# ISPnub_v1_1.net
KiCad netlist of a schematic drawn in EAGLE
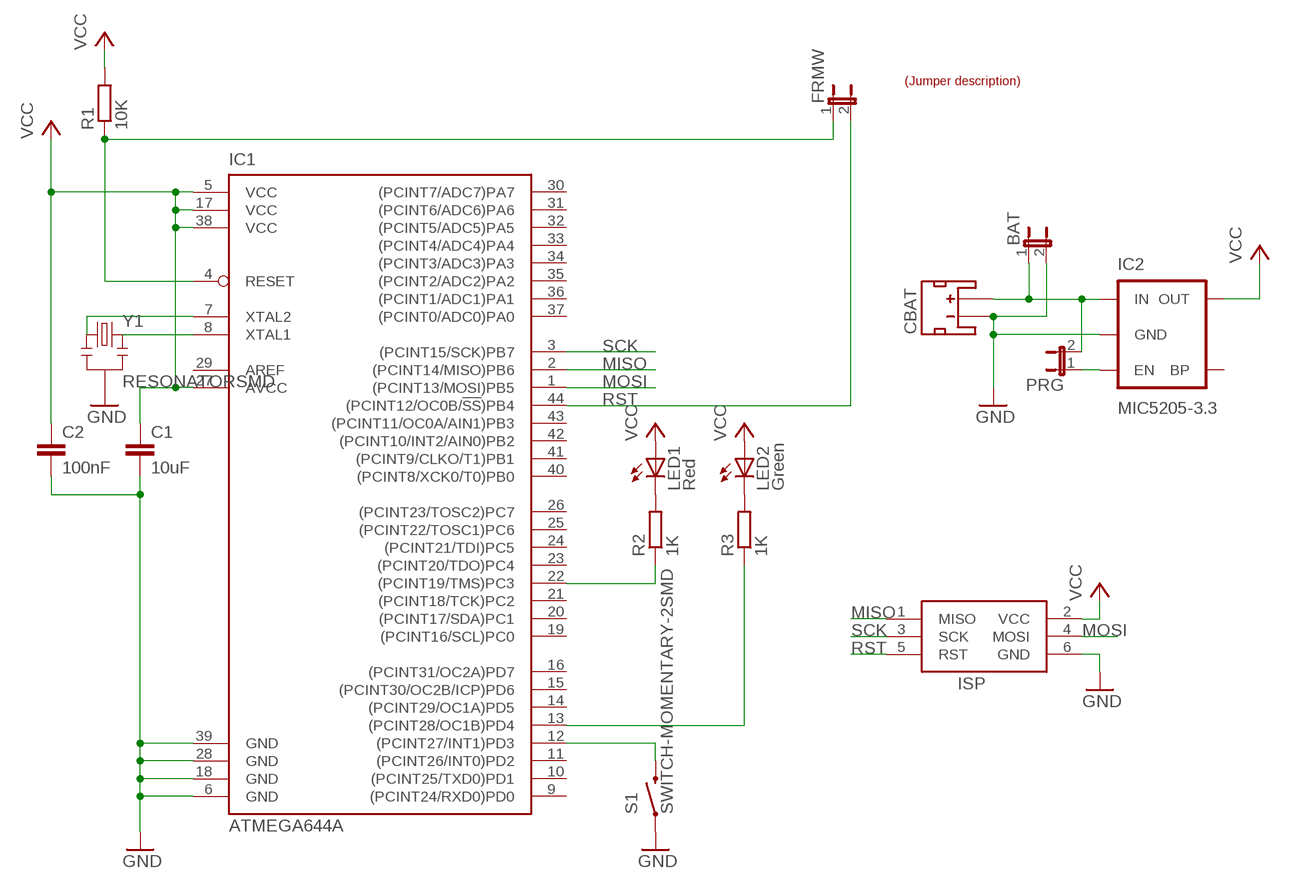
[diagram p0: schematic, sheet 1]

(export (version "E")
  (design (tool "Eeschema 10.0.6"))
  (components
    (comp (ref "BAT")
      (value "JP1E")
      (footprint "eagle-import:JP1")
      (libsource (lib "eagle-import") (part "JP1E"))
    )
    (comp (ref "C1")
      (value "10uF")
      (footprint "eagle-import:C0805")
      (libsource (lib "eagle-import") (part "C-EUC0805"))
    )
    (comp (ref "C2")
      (value "100nF")
      (footprint "eagle-import:C0805")
      (libsource (lib "eagle-import") (part "C-EUC0805"))
    )
    (comp (ref "CBAT")
      (value "JST PH SMT")
      (footprint "eagle-import:JST-2-SMD")
      (libsource (lib "eagle-import") (part "JST_2MM_MALE"))
    )
    (comp (ref "FRMW")
      (value "JP1E")
      (footprint "eagle-import:JP1")
      (libsource (lib "eagle-import") (part "JP1E"))
    )
    (comp (ref "IC1")
      (value "ATMEGA644A")
      (footprint "eagle-import:TQFP44")
      (fields (field (name "MPN") "ATMEGA644PV-10AU") (field (name "MPN_1") "ATMEGA1284PV-10AU"))
      (libsource (lib "eagle-import") (part "ATMEGA644A"))
    )
    (comp (ref "IC2")
      (value "MIC5205-3.3")
      (footprint "eagle-import:SOT23-5")
      (libsource (lib "eagle-import") (part "V_REG_LDOSMD"))
    )
    (comp (ref "ISP")
      (value "AVRISP-6")
      (footprint "eagle-import:AVRISP")
      (libsource (lib "eagle-import") (part "AVRISP-6"))
    )
    (comp (ref "LED1")
      (value "Red")
      (footprint "eagle-import:CHIP-LED0805")
      (libsource (lib "eagle-import") (part "LEDCHIP-LED0805"))
    )
    (comp (ref "LED2")
      (value "Green")
      (footprint "eagle-import:CHIP-LED0805")
      (libsource (lib "eagle-import") (part "LEDCHIP-LED0805"))
    )
    (comp (ref "PRG")
      (value "JP1E")
      (footprint "eagle-import:JP1")
      (libsource (lib "eagle-import") (part "JP1E"))
    )
    (comp (ref "R1")
      (value "10K")
      (footprint "eagle-import:R0805")
      (libsource (lib "eagle-import") (part "R-EU_R0805"))
    )
    (comp (ref "R2")
      (value "1K")
      (footprint "eagle-import:R0805")
      (libsource (lib "eagle-import") (part "R-EU_R0805"))
    )
    (comp (ref "R3")
      (value "1K")
      (footprint "eagle-import:R0805")
      (libsource (lib "eagle-import") (part "R-EU_R0805"))
    )
    (comp (ref "S1")
      (value "SWITCH-MOMENTARY-2SMD")
      (footprint "eagle-import:TACTILE_SWITCH_SMD")
      (libsource (lib "eagle-import") (part "SWITCH-MOMENTARY-2SMD"))
    )
    (comp (ref "U$1")
      (value "LABEL_JUMPER_1X2")
      (footprint "eagle-import:JUMP2_DESC")
      (fields (field (name "OFF") "Normal") (field (name "ON") "Update Firmware"))
      (libsource (lib "eagle-import") (part "LABEL_JUMPER_1X2"))
    )
    (comp (ref "Y1")
      (value "RESONATORSMD")
      (footprint "eagle-import:RESONATOR-SMD")
      (libsource (lib "eagle-import") (part "RESONATORSMD"))
    )
  )
  (nets
    (net (code "1") (name "/MISO") (class "Default")
      (node (ref "IC1") (pin "2") (pinfunction "(PCINT14/MISO)PB6_2") (pintype "bidirectional"))
      (node (ref "ISP") (pin "1") (pinfunction "MISO_1") (pintype "input"))
    )
    (net (code "2") (name "/MOSI") (class "Default")
      (node (ref "IC1") (pin "1") (pinfunction "(PCINT13/MOSI)PB5_1") (pintype "bidirectional"))
      (node (ref "ISP") (pin "4") (pinfunction "MOSI_4") (pintype "output"))
    )
    (net (code "3") (name "/RST") (class "Default")
      (node (ref "FRMW") (pin "2") (pinfunction "2_2") (pintype "passive"))
      (node (ref "IC1") (pin "44") (pinfunction "(PCINT12/OC0B/~{SS})PB4_44") (pintype "bidirectional"))
      (node (ref "ISP") (pin "5") (pinfunction "RST_5") (pintype "output"))
    )
    (net (code "4") (name "/SCK") (class "Default")
      (node (ref "IC1") (pin "3") (pinfunction "(PCINT15/SCK)PB7_3") (pintype "bidirectional"))
      (node (ref "ISP") (pin "3") (pinfunction "SCK_3") (pintype "output"))
    )
    (net (code "5") (name "GND") (class "Default")
      (node (ref "BAT") (pin "2") (pinfunction "2_2") (pintype "passive"))
      (node (ref "C1") (pin "2") (pinfunction "2_2") (pintype "passive"))
      (node (ref "C2") (pin "2") (pinfunction "2_2") (pintype "passive"))
      (node (ref "CBAT") (pin "1") (pinfunction "-_1") (pintype "bidirectional"))
      (node (ref "IC1") (pin "18") (pinfunction "GND_18") (pintype "power_in"))
      (node (ref "IC1") (pin "28") (pinfunction "GND_28") (pintype "power_in"))
      (node (ref "IC1") (pin "39") (pinfunction "GND_39") (pintype "power_in"))
      (node (ref "IC1") (pin "6") (pinfunction "GND_6") (pintype "power_in"))
      (node (ref "IC2") (pin "2") (pinfunction "GND_2") (pintype "input"))
      (node (ref "ISP") (pin "6") (pinfunction "GND_6") (pintype "power_in"))
      (node (ref "S1") (pin "1") (pinfunction "1_1") (pintype "passive"))
      (node (ref "Y1") (pin "2") (pinfunction "2_2") (pintype "passive"))
    )
    (net (code "6") (name "Net-(CBAT-+)") (class "Default")
      (node (ref "BAT") (pin "1") (pinfunction "1_1") (pintype "passive"))
      (node (ref "CBAT") (pin "2") (pinfunction "+_2") (pintype "bidirectional"))
      (node (ref "IC2") (pin "1") (pinfunction "IN_1") (pintype "input"))
      (node (ref "PRG") (pin "2") (pinfunction "2_2") (pintype "passive"))
    )
    (net (code "7") (name "Net-(IC1-(PCINT19{slash}TMS)PC3)") (class "Default")
      (node (ref "IC1") (pin "22") (pinfunction "(PCINT19/TMS)PC3_22") (pintype "output"))
      (node (ref "R2") (pin "1") (pinfunction "1_1") (pintype "passive"))
    )
    (net (code "8") (name "Net-(IC1-(PCINT27{slash}INT1)PD3)") (class "Default")
      (node (ref "IC1") (pin "12") (pinfunction "(PCINT27/INT1)PD3_12") (pintype "bidirectional"))
      (node (ref "S1") (pin "3") (pinfunction "2_3") (pintype "passive"))
    )
    (net (code "9") (name "Net-(IC1-(PCINT28{slash}OC1B)PD4)") (class "Default")
      (node (ref "IC1") (pin "13") (pinfunction "(PCINT28/OC1B)PD4_13") (pintype "bidirectional"))
      (node (ref "R3") (pin "1") (pinfunction "1_1") (pintype "passive"))
    )
    (net (code "10") (name "Net-(IC1-RESET)") (class "Default")
      (node (ref "FRMW") (pin "1") (pinfunction "1_1") (pintype "passive"))
      (node (ref "IC1") (pin "4") (pinfunction "RESET_4") (pintype "input"))
      (node (ref "R1") (pin "1") (pinfunction "1_1") (pintype "passive"))
    )
    (net (code "11") (name "Net-(IC1-XTAL1)") (class "Default")
      (node (ref "IC1") (pin "8") (pinfunction "XTAL1_8") (pintype "bidirectional"))
      (node (ref "Y1") (pin "3") (pinfunction "3_3") (pintype "passive"))
    )
    (net (code "12") (name "Net-(IC1-XTAL2)") (class "Default")
      (node (ref "IC1") (pin "7") (pinfunction "XTAL2_7") (pintype "bidirectional"))
      (node (ref "Y1") (pin "1") (pinfunction "1_1") (pintype "passive"))
    )
    (net (code "13") (name "Net-(IC2-EN)") (class "Default")
      (node (ref "IC2") (pin "3") (pinfunction "EN_3") (pintype "input"))
      (node (ref "PRG") (pin "1") (pinfunction "1_1") (pintype "passive"))
    )
    (net (code "14") (name "Net-(LED1-PadC)") (class "Default")
      (node (ref "LED1") (pin "C") (pinfunction "C_C") (pintype "passive"))
      (node (ref "R2") (pin "2") (pinfunction "2_2") (pintype "passive"))
    )
    (net (code "15") (name "Net-(LED2-PadC)") (class "Default")
      (node (ref "LED2") (pin "C") (pinfunction "C_C") (pintype "passive"))
      (node (ref "R3") (pin "2") (pinfunction "2_2") (pintype "passive"))
    )
    (net (code "16") (name "VCC") (class "Default")
      (node (ref "C1") (pin "1") (pinfunction "1_1") (pintype "passive"))
      (node (ref "C2") (pin "1") (pinfunction "1_1") (pintype "passive"))
      (node (ref "IC1") (pin "17") (pinfunction "VCC_17") (pintype "power_in"))
      (node (ref "IC1") (pin "27") (pinfunction "AVCC_27") (pintype "power_in"))
      (node (ref "IC1") (pin "38") (pinfunction "VCC_38") (pintype "power_in"))
      (node (ref "IC1") (pin "5") (pinfunction "VCC_5") (pintype "power_in"))
      (node (ref "IC2") (pin "5") (pinfunction "OUT_5") (pintype "passive"))
      (node (ref "ISP") (pin "2") (pinfunction "VCC_2") (pintype "power_in"))
      (node (ref "LED1") (pin "A") (pinfunction "A_A") (pintype "passive"))
      (node (ref "LED2") (pin "A") (pinfunction "A_A") (pintype "passive"))
      (node (ref "R1") (pin "2") (pinfunction "2_2") (pintype "passive"))
    )
    (net (code "17") (name "unconnected-(CBAT-PAD1-PadNC1)") (class "Default")
      (node (ref "CBAT") (pin "NC1") (pinfunction "PAD1_NC1") (pintype "bidirectional"))
    )
    (net (code "18") (name "unconnected-(CBAT-PAD2-PadNC2)") (class "Default")
      (node (ref "CBAT") (pin "NC2") (pinfunction "PAD2_NC2") (pintype "bidirectional"))
    )
    (net (code "19") (name "unconnected-(IC1-(PCINT0{slash}ADC0)PA0-Pad37)") (class "Default")
      (node (ref "IC1") (pin "37") (pinfunction "(PCINT0/ADC0)PA0_37") (pintype "bidirectional"))
    )
    (net (code "20") (name "unconnected-(IC1-(PCINT1{slash}ADC1)PA1-Pad36)") (class "Default")
      (node (ref "IC1") (pin "36") (pinfunction "(PCINT1/ADC1)PA1_36") (pintype "bidirectional"))
    )
    (net (code "21") (name "unconnected-(IC1-(PCINT2{slash}ADC2)PA2-Pad35)") (class "Default")
      (node (ref "IC1") (pin "35") (pinfunction "(PCINT2/ADC2)PA2_35") (pintype "bidirectional"))
    )
    (net (code "22") (name "unconnected-(IC1-(PCINT3{slash}ADC3)PA3-Pad34)") (class "Default")
      (node (ref "IC1") (pin "34") (pinfunction "(PCINT3/ADC3)PA3_34") (pintype "bidirectional"))
    )
    (net (code "23") (name "unconnected-(IC1-(PCINT4{slash}ADC4)PA4-Pad33)") (class "Default")
      (node (ref "IC1") (pin "33") (pinfunction "(PCINT4/ADC4)PA4_33") (pintype "bidirectional"))
    )
    (net (code "24") (name "unconnected-(IC1-(PCINT5{slash}ADC5)PA5-Pad32)") (class "Default")
      (node (ref "IC1") (pin "32") (pinfunction "(PCINT5/ADC5)PA5_32") (pintype "bidirectional"))
    )
    (net (code "25") (name "unconnected-(IC1-(PCINT6{slash}ADC6)PA6-Pad31)") (class "Default")
      (node (ref "IC1") (pin "31") (pinfunction "(PCINT6/ADC6)PA6_31") (pintype "bidirectional"))
    )
    (net (code "26") (name "unconnected-(IC1-(PCINT7{slash}ADC7)PA7-Pad30)") (class "Default")
      (node (ref "IC1") (pin "30") (pinfunction "(PCINT7/ADC7)PA7_30") (pintype "bidirectional"))
    )
    (net (code "27") (name "unconnected-(IC1-(PCINT8{slash}XCK0{slash}T0)PB0-Pad40)") (class "Default")
      (node (ref "IC1") (pin "40") (pinfunction "(PCINT8/XCK0/T0)PB0_40") (pintype "bidirectional"))
    )
    (net (code "28") (name "unconnected-(IC1-(PCINT9{slash}CLKO{slash}T1)PB1-Pad41)") (class "Default")
      (node (ref "IC1") (pin "41") (pinfunction "(PCINT9/CLKO/T1)PB1_41") (pintype "bidirectional"))
    )
    (net (code "29") (name "unconnected-(IC1-(PCINT10{slash}INT2{slash}AIN0)PB2-Pad42)") (class "Default")
      (node (ref "IC1") (pin "42") (pinfunction "(PCINT10/INT2/AIN0)PB2_42") (pintype "bidirectional"))
    )
    (net (code "30") (name "unconnected-(IC1-(PCINT11{slash}OC0A{slash}AIN1)PB3-Pad43)") (class "Default")
      (node (ref "IC1") (pin "43") (pinfunction "(PCINT11/OC0A/AIN1)PB3_43") (pintype "bidirectional"))
    )
    (net (code "31") (name "unconnected-(IC1-(PCINT16{slash}SCL)PC0-Pad19)") (class "Default")
      (node (ref "IC1") (pin "19") (pinfunction "(PCINT16/SCL)PC0_19") (pintype "output"))
    )
    (net (code "32") (name "unconnected-(IC1-(PCINT17{slash}SDA)PC1-Pad20)") (class "Default")
      (node (ref "IC1") (pin "20") (pinfunction "(PCINT17/SDA)PC1_20") (pintype "output"))
    )
    (net (code "33") (name "unconnected-(IC1-(PCINT18{slash}TCK)PC2-Pad21)") (class "Default")
      (node (ref "IC1") (pin "21") (pinfunction "(PCINT18/TCK)PC2_21") (pintype "output"))
    )
    (net (code "34") (name "unconnected-(IC1-(PCINT20{slash}TDO)PC4-Pad23)") (class "Default")
      (node (ref "IC1") (pin "23") (pinfunction "(PCINT20/TDO)PC4_23") (pintype "output"))
    )
    (net (code "35") (name "unconnected-(IC1-(PCINT21{slash}TDI)PC5-Pad24)") (class "Default")
      (node (ref "IC1") (pin "24") (pinfunction "(PCINT21/TDI)PC5_24") (pintype "output"))
    )
    (net (code "36") (name "unconnected-(IC1-(PCINT22{slash}TOSC1)PC6-Pad25)") (class "Default")
      (node (ref "IC1") (pin "25") (pinfunction "(PCINT22/TOSC1)PC6_25") (pintype "output"))
    )
    (net (code "37") (name "unconnected-(IC1-(PCINT23{slash}TOSC2)PC7-Pad26)") (class "Default")
      (node (ref "IC1") (pin "26") (pinfunction "(PCINT23/TOSC2)PC7_26") (pintype "output"))
    )
    (net (code "38") (name "unconnected-(IC1-(PCINT24{slash}RXD0)PD0-Pad9)") (class "Default")
      (node (ref "IC1") (pin "9") (pinfunction "(PCINT24/RXD0)PD0_9") (pintype "bidirectional"))
    )
    (net (code "39") (name "unconnected-(IC1-(PCINT25{slash}TXD0)PD1-Pad10)") (class "Default")
      (node (ref "IC1") (pin "10") (pinfunction "(PCINT25/TXD0)PD1_10") (pintype "bidirectional"))
    )
    (net (code "40") (name "unconnected-(IC1-(PCINT26{slash}INT0)PD2-Pad11)") (class "Default")
      (node (ref "IC1") (pin "11") (pinfunction "(PCINT26/INT0)PD2_11") (pintype "bidirectional"))
    )
    (net (code "41") (name "unconnected-(IC1-(PCINT29{slash}OC1A)PD5-Pad14)") (class "Default")
      (node (ref "IC1") (pin "14") (pinfunction "(PCINT29/OC1A)PD5_14") (pintype "bidirectional"))
    )
    (net (code "42") (name "unconnected-(IC1-(PCINT30{slash}OC2B{slash}ICP)PD6-Pad15)") (class "Default")
      (node (ref "IC1") (pin "15") (pinfunction "(PCINT30/OC2B/ICP)PD6_15") (pintype "bidirectional"))
    )
    (net (code "43") (name "unconnected-(IC1-(PCINT31{slash}OC2A)PD7-Pad16)") (class "Default")
      (node (ref "IC1") (pin "16") (pinfunction "(PCINT31/OC2A)PD7_16") (pintype "bidirectional"))
    )
    (net (code "44") (name "unconnected-(IC1-AREF-Pad29)") (class "Default")
      (node (ref "IC1") (pin "29") (pinfunction "AREF_29") (pintype "passive"))
    )
    (net (code "45") (name "unconnected-(IC2-BP-Pad4)") (class "Default")
      (node (ref "IC2") (pin "4") (pinfunction "BP_4") (pintype "input"))
    )
  )
)
